# PLL.net
KiCad netlist of a schematic drawn in Altium Designer
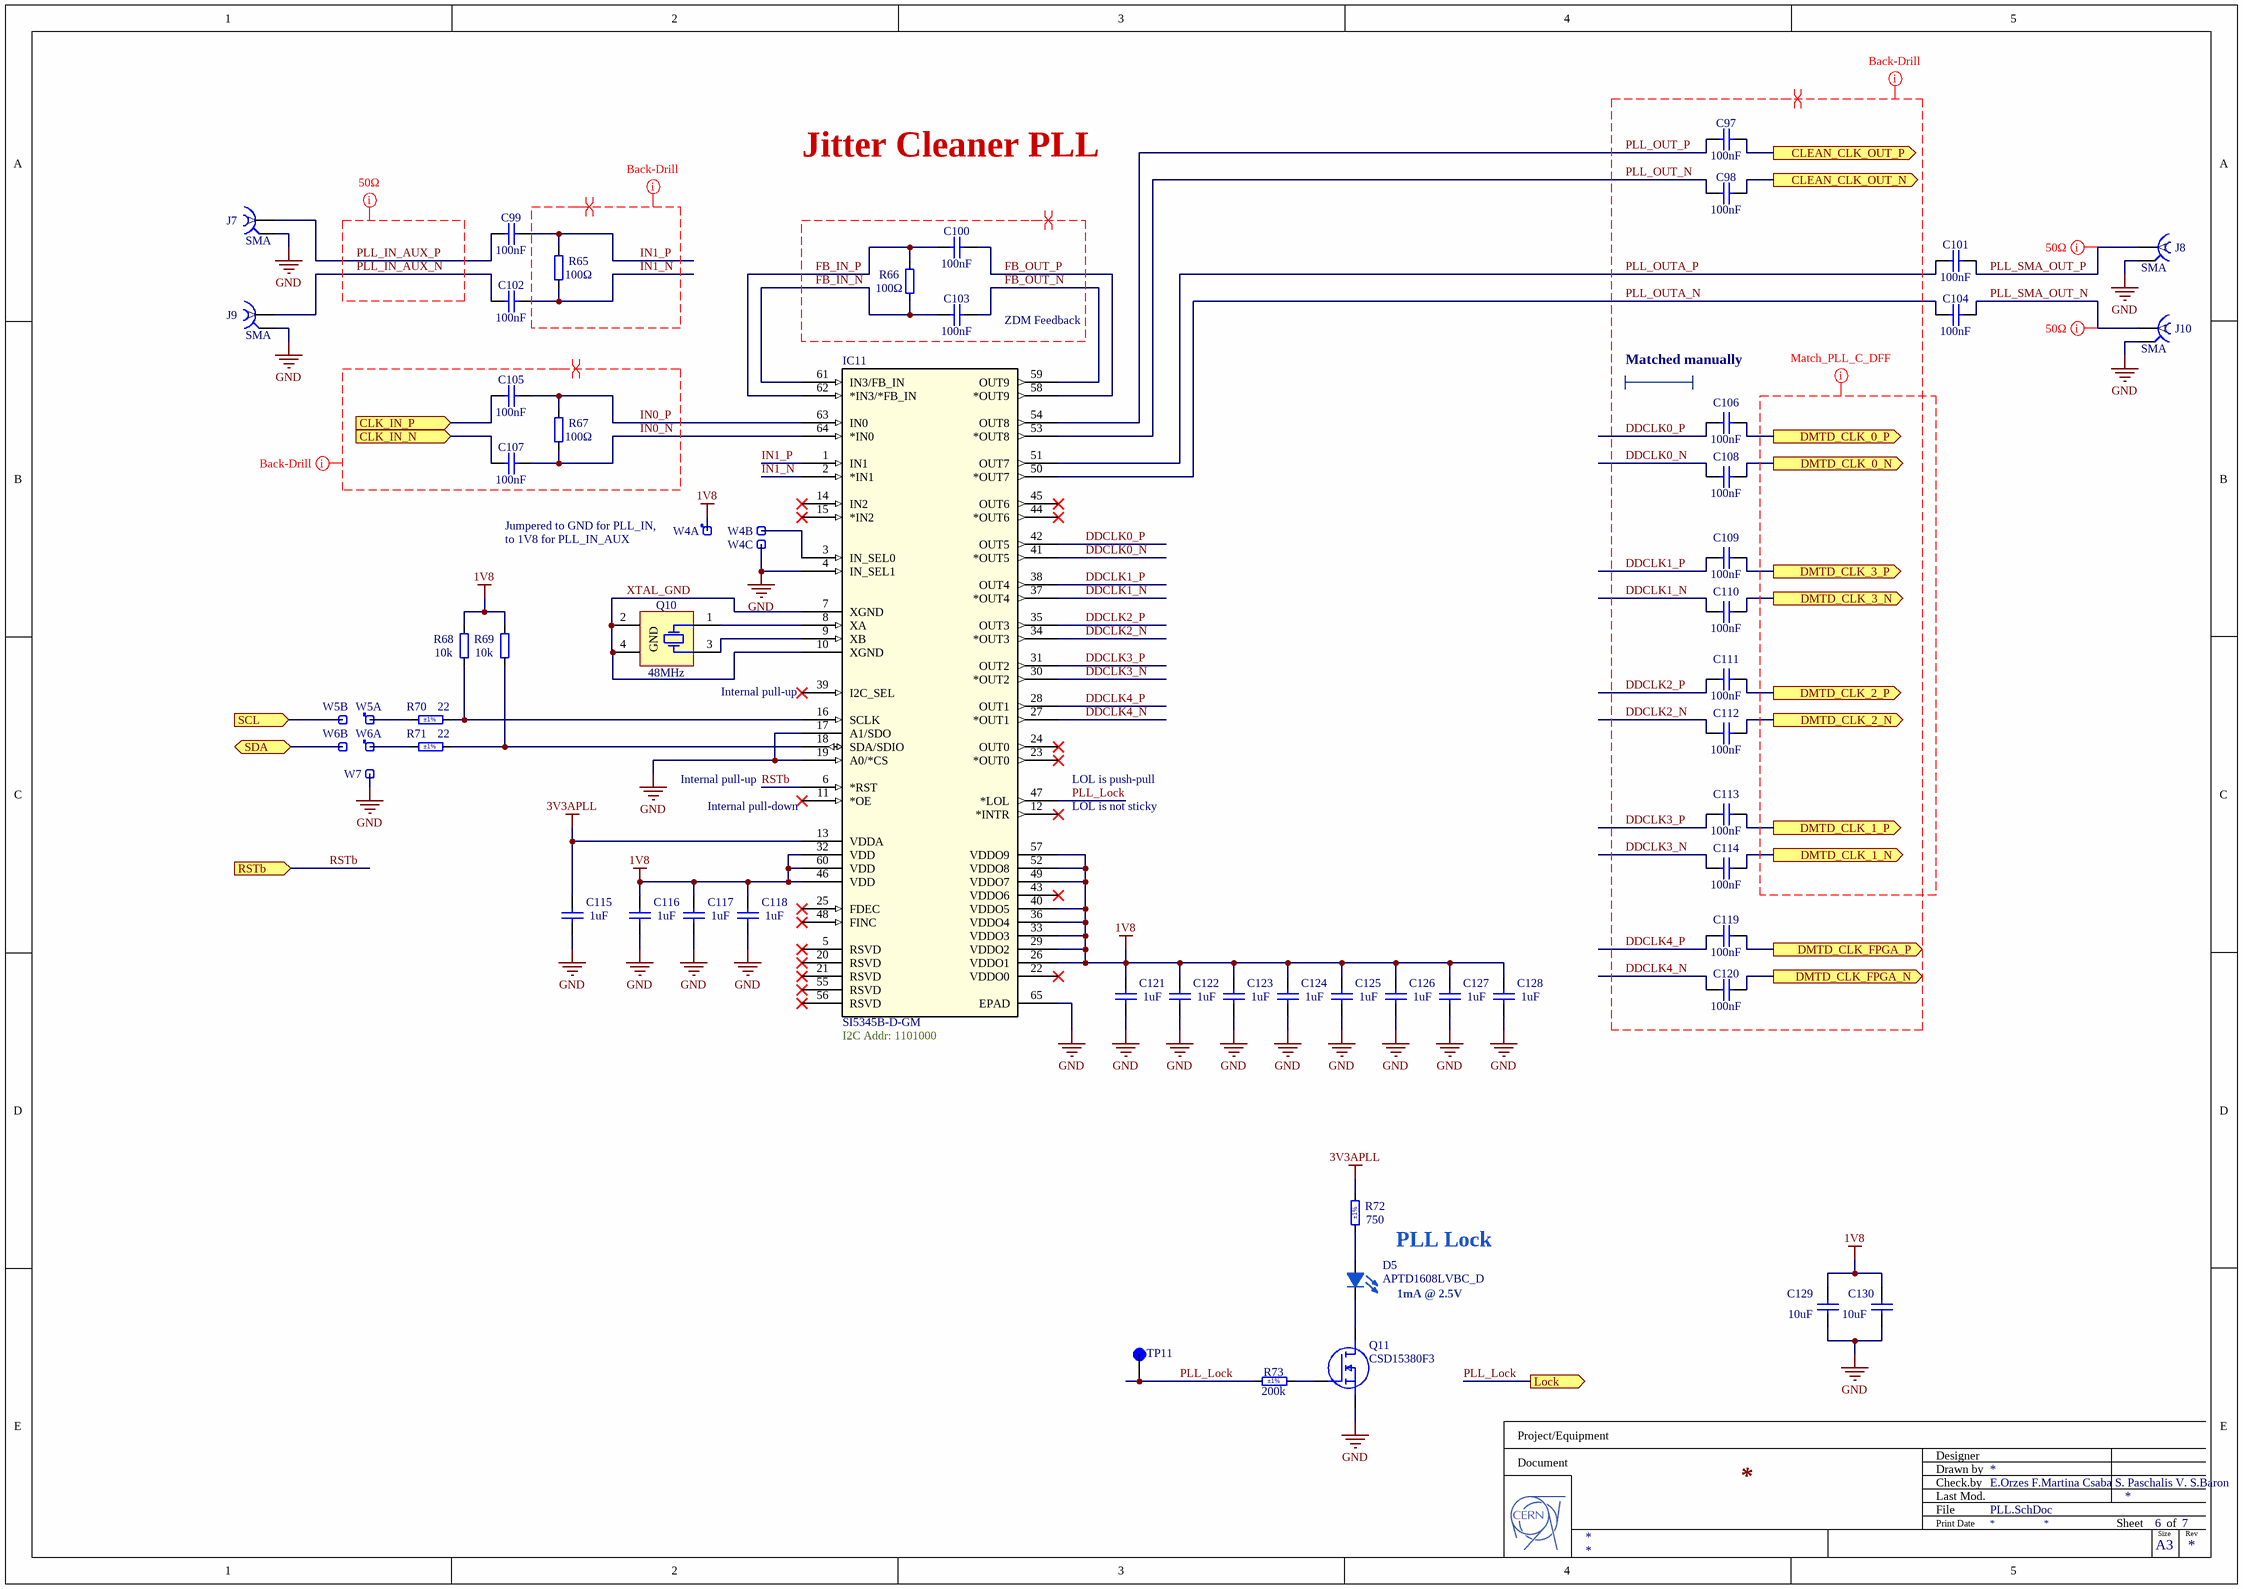
[diagram p0: PLL.SchDoc]

(export (version "E")
  (design (tool "Eeschema 10.0.6"))
  (components
    (comp (ref "C97")
      (value "100nF")
      (footprint "MURATA_HI_DENSITY_0201")
      (description "GRM033R61C104KE14")
      (libsource (lib "schLib") (part "C0201-100nF-high-density"))
    )
    (comp (ref "C98")
      (value "100nF")
      (footprint "MURATA_HI_DENSITY_0201")
      (description "GRM033R61C104KE14")
      (libsource (lib "schLib") (part "C0201-100nF-high-density"))
    )
    (comp (ref "C99")
      (value "100nF")
      (footprint "MURATA_HI_DENSITY_0201")
      (description "GRM033R61C104KE14")
      (libsource (lib "schLib") (part "C0201-100nF-high-density"))
    )
    (comp (ref "C100")
      (value "100nF")
      (footprint "MURATA_HI_DENSITY_0201")
      (description "GRM033R61C104KE14")
      (libsource (lib "schLib") (part "C0201-100nF-high-density"))
    )
    (comp (ref "C101")
      (value "100nF")
      (footprint "MURATA_HI_DENSITY_0201")
      (description "GRM033R61C104KE14")
      (libsource (lib "schLib") (part "C0201-100nF-high-density"))
    )
    (comp (ref "C102")
      (value "100nF")
      (footprint "MURATA_HI_DENSITY_0201")
      (description "GRM033R61C104KE14")
      (libsource (lib "schLib") (part "C0201-100nF-high-density"))
    )
    (comp (ref "C103")
      (value "100nF")
      (footprint "MURATA_HI_DENSITY_0201")
      (description "GRM033R61C104KE14")
      (libsource (lib "schLib") (part "C0201-100nF-high-density"))
    )
    (comp (ref "C104")
      (value "100nF")
      (footprint "MURATA_HI_DENSITY_0201")
      (description "GRM033R61C104KE14")
      (libsource (lib "schLib") (part "C0201-100nF-high-density"))
    )
    (comp (ref "C105")
      (value "100nF")
      (footprint "MURATA_HI_DENSITY_0201")
      (description "GRM033R61C104KE14")
      (libsource (lib "schLib") (part "C0201-100nF-high-density"))
    )
    (comp (ref "C106")
      (value "100nF")
      (footprint "MURATA_HI_DENSITY_0201")
      (description "GRM033R61C104KE14")
      (libsource (lib "schLib") (part "C0201-100nF-high-density"))
    )
    (comp (ref "C107")
      (value "100nF")
      (footprint "MURATA_HI_DENSITY_0201")
      (description "GRM033R61C104KE14")
      (libsource (lib "schLib") (part "C0201-100nF-high-density"))
    )
    (comp (ref "C108")
      (value "100nF")
      (footprint "MURATA_HI_DENSITY_0201")
      (description "GRM033R61C104KE14")
      (libsource (lib "schLib") (part "C0201-100nF-high-density"))
    )
    (comp (ref "C109")
      (value "100nF")
      (footprint "MURATA_HI_DENSITY_0201")
      (description "GRM033R61C104KE14")
      (libsource (lib "schLib") (part "C0201-100nF-high-density"))
    )
    (comp (ref "C110")
      (value "100nF")
      (footprint "MURATA_HI_DENSITY_0201")
      (description "GRM033R61C104KE14")
      (libsource (lib "schLib") (part "C0201-100nF-high-density"))
    )
    (comp (ref "C111")
      (value "100nF")
      (footprint "MURATA_HI_DENSITY_0201")
      (description "GRM033R61C104KE14")
      (libsource (lib "schLib") (part "C0201-100nF-high-density"))
    )
    (comp (ref "C112")
      (value "100nF")
      (footprint "MURATA_HI_DENSITY_0201")
      (description "GRM033R61C104KE14")
      (libsource (lib "schLib") (part "C0201-100nF-high-density"))
    )
    (comp (ref "C113")
      (value "100nF")
      (footprint "MURATA_HI_DENSITY_0201")
      (description "GRM033R61C104KE14")
      (libsource (lib "schLib") (part "C0201-100nF-high-density"))
    )
    (comp (ref "C114")
      (value "100nF")
      (footprint "MURATA_HI_DENSITY_0201")
      (description "GRM033R61C104KE14")
      (libsource (lib "schLib") (part "C0201-100nF-high-density"))
    )
    (comp (ref "C115")
      (value "1uF")
      (footprint "CAPC1005X55N")
      (description "GRM153B30J105ME15")
      (fields
        (field (name "PART NUMBER") "CC0402_1UF_16V_10%_X5R")
        (field (name "VOLTAGE") "16V")
        (field (name "AUTHOR") "CERN DEM JLC")
      )
      (libsource (lib "Capacitors") (part "Capacitor - non polarized"))
    )
    (comp (ref "C116")
      (value "1uF")
      (footprint "CAPC1005X55N")
      (description "GRM153B30J105ME15")
      (fields
        (field (name "PART NUMBER") "CC0402_1UF_16V_10%_X5R")
        (field (name "VOLTAGE") "16V")
        (field (name "AUTHOR") "CERN DEM JLC")
      )
      (libsource (lib "Capacitors") (part "Capacitor - non polarized"))
    )
    (comp (ref "C117")
      (value "1uF")
      (footprint "CAPC1005X55N")
      (description "GRM153B30J105ME15")
      (fields
        (field (name "PART NUMBER") "CC0402_1UF_16V_10%_X5R")
        (field (name "VOLTAGE") "16V")
        (field (name "AUTHOR") "CERN DEM JLC")
      )
      (libsource (lib "Capacitors") (part "Capacitor - non polarized"))
    )
    (comp (ref "C118")
      (value "1uF")
      (footprint "CAPC1005X55N")
      (description "GRM153B30J105ME15")
      (fields
        (field (name "PART NUMBER") "CC0402_1UF_16V_10%_X5R")
        (field (name "VOLTAGE") "16V")
        (field (name "AUTHOR") "CERN DEM JLC")
      )
      (libsource (lib "Capacitors") (part "Capacitor - non polarized"))
    )
    (comp (ref "C119")
      (value "100nF")
      (footprint "MURATA_HI_DENSITY_0201")
      (description "GRM033R61C104KE14")
      (libsource (lib "schLib") (part "C0201-100nF-high-density"))
    )
    (comp (ref "C120")
      (value "100nF")
      (footprint "MURATA_HI_DENSITY_0201")
      (description "GRM033R61C104KE14")
      (libsource (lib "schLib") (part "C0201-100nF-high-density"))
    )
    (comp (ref "C121")
      (value "1uF")
      (footprint "CAPC1005X55N")
      (description "GRM153B30J105ME15")
      (fields
        (field (name "PART NUMBER") "CC0402_1UF_16V_10%_X5R")
        (field (name "VOLTAGE") "16V")
        (field (name "AUTHOR") "CERN DEM JLC")
      )
      (libsource (lib "Capacitors") (part "Capacitor - non polarized"))
    )
    (comp (ref "C122")
      (value "1uF")
      (footprint "CAPC1005X55N")
      (description "GRM153B30J105ME15")
      (fields
        (field (name "PART NUMBER") "CC0402_1UF_16V_10%_X5R")
        (field (name "VOLTAGE") "16V")
        (field (name "AUTHOR") "CERN DEM JLC")
      )
      (libsource (lib "Capacitors") (part "Capacitor - non polarized"))
    )
    (comp (ref "C123")
      (value "1uF")
      (footprint "CAPC1005X55N")
      (description "GRM153B30J105ME15")
      (fields
        (field (name "PART NUMBER") "CC0402_1UF_16V_10%_X5R")
        (field (name "VOLTAGE") "16V")
        (field (name "AUTHOR") "CERN DEM JLC")
      )
      (libsource (lib "Capacitors") (part "Capacitor - non polarized"))
    )
    (comp (ref "C124")
      (value "1uF")
      (footprint "CAPC1005X55N")
      (description "GRM153B30J105ME15")
      (fields
        (field (name "PART NUMBER") "CC0402_1UF_16V_10%_X5R")
        (field (name "VOLTAGE") "16V")
        (field (name "AUTHOR") "CERN DEM JLC")
      )
      (libsource (lib "Capacitors") (part "Capacitor - non polarized"))
    )
    (comp (ref "C125")
      (value "1uF")
      (footprint "CAPC1005X55N")
      (description "GRM153B30J105ME15")
      (fields
        (field (name "PART NUMBER") "CC0402_1UF_16V_10%_X5R")
        (field (name "VOLTAGE") "16V")
        (field (name "AUTHOR") "CERN DEM JLC")
      )
      (libsource (lib "Capacitors") (part "Capacitor - non polarized"))
    )
    (comp (ref "C126")
      (value "1uF")
      (footprint "CAPC1005X55N")
      (description "GRM153B30J105ME15")
      (fields
        (field (name "PART NUMBER") "CC0402_1UF_16V_10%_X5R")
        (field (name "VOLTAGE") "16V")
        (field (name "AUTHOR") "CERN DEM JLC")
      )
      (libsource (lib "Capacitors") (part "Capacitor - non polarized"))
    )
    (comp (ref "C127")
      (value "1uF")
      (footprint "CAPC1005X55N")
      (description "GRM153B30J105ME15")
      (fields
        (field (name "PART NUMBER") "CC0402_1UF_16V_10%_X5R")
        (field (name "VOLTAGE") "16V")
        (field (name "AUTHOR") "CERN DEM JLC")
      )
      (libsource (lib "Capacitors") (part "Capacitor - non polarized"))
    )
    (comp (ref "C128")
      (value "1uF")
      (footprint "CAPC1005X55N")
      (description "GRM153B30J105ME15")
      (fields
        (field (name "PART NUMBER") "CC0402_1UF_16V_10%_X5R")
        (field (name "VOLTAGE") "16V")
        (field (name "AUTHOR") "CERN DEM JLC")
      )
      (libsource (lib "Capacitors") (part "Capacitor - non polarized"))
    )
    (comp (ref "C129")
      (value "10uF")
      (footprint "CAPC1608X87N")
      (description "C1608X5R1E106M080AC")
      (fields
        (field (name "PART NUMBER") "CC0603_10UF_6.3V_20%_X5R")
        (field (name "VOLTAGE") "6.3V")
        (field (name "AUTHOR") "CERN DEM JLC")
      )
      (libsource (lib "Capacitors") (part "Capacitor - non polarized"))
    )
    (comp (ref "C130")
      (value "10uF")
      (footprint "CAPC1608X87N")
      (description "C1608X5R1E106M080AC")
      (fields
        (field (name "PART NUMBER") "CC0603_10UF_6.3V_20%_X5R")
        (field (name "VOLTAGE") "6.3V")
        (field (name "AUTHOR") "CERN DEM JLC")
      )
      (libsource (lib "Capacitors") (part "Capacitor - non polarized"))
    )
    (comp (ref "D5")
      (value "APTD1608LVBC_D")
      (footprint "SamacSys:LEDC1608X110N")
      (description "LED")
      (fields
        (field (name "MANUFACTURER_PART_NUMBER") "APTD1608LVBC/D")
        (field (name "MOUSER PART NUMBER") "604-APTD1608LVBCD")
      )
      (libsource (lib "SamacSys") (part "APTD1608LVBC_D"))
    )
    (comp (ref "IC11")
      (value "SI5345B-D-GM")
      (footprint "SamacSys:QFN50P900X900X90-65N-D")
      (description "Integrated Circuit")
      (fields (field (name "MOUSER PART NUMBER") "634-SI5345B-D-GM"))
      (libsource (lib "SamacSys") (part "SI5345B-D-GM"))
    )
    (comp (ref "J7")
      (value "SMA")
      (footprint "SAMTEC_SMA-J-P-H-ST-MT1")
      (fields
        (field (name "PART NUMBER") "SAMTEC_SMA-J-P-H-ST-MT1")
        (field (name "MANUFACTURER") "SAMTEC")
        (field (name "MANUFACTURER PART NUMBER") "SMA-J-P-H-ST-MT1")
        (field (name "AUTHOR") "CERN DEM HF")
      )
      (libsource (lib "") (part "Coax_1Female_1Shield_1"))
    )
    (comp (ref "J8")
      (value "SMA")
      (footprint "SAMTEC_SMA-J-P-H-ST-MT1")
      (fields
        (field (name "PART NUMBER") "SAMTEC_SMA-J-P-H-ST-MT1")
        (field (name "MANUFACTURER") "SAMTEC")
        (field (name "MANUFACTURER PART NUMBER") "SMA-J-P-H-ST-MT1")
        (field (name "AUTHOR") "CERN DEM HF")
      )
      (libsource (lib "Connectors") (part "Coax_1Female_1Shield"))
    )
    (comp (ref "J9")
      (value "SMA")
      (footprint "SAMTEC_SMA-J-P-H-ST-MT1")
      (fields
        (field (name "PART NUMBER") "SAMTEC_SMA-J-P-H-ST-MT1")
        (field (name "MANUFACTURER") "SAMTEC")
        (field (name "MANUFACTURER PART NUMBER") "SMA-J-P-H-ST-MT1")
        (field (name "AUTHOR") "CERN DEM HF")
      )
      (libsource (lib "") (part "Coax_1Female_1Shield_1"))
    )
    (comp (ref "J10")
      (value "SMA")
      (footprint "SAMTEC_SMA-J-P-H-ST-MT1")
      (fields
        (field (name "PART NUMBER") "SAMTEC_SMA-J-P-H-ST-MT1")
        (field (name "MANUFACTURER") "SAMTEC")
        (field (name "MANUFACTURER PART NUMBER") "SMA-J-P-H-ST-MT1")
        (field (name "AUTHOR") "CERN DEM HF")
      )
      (libsource (lib "Connectors") (part "Coax_1Female_1Shield"))
    )
    (comp (ref "Q10")
      (value "48MHz")
      (footprint "XTAL_KYOCERA_CX3225SB")
      (description "Crystal 4 pins 1=XTAL Control 2=GND3=XTAL 4=GND")
      (fields
        (field (name "PART NUMBER") "XTAL_48MHZ_KYOCERA_CX3225SB48000D0FPJC1")
        (field (name "MANUFACTURER") "KYOCERA")
        (field (name "AUTHOR") "CERN DEM JLC")
      )
      (libsource (lib "ICs And Semiconductors") (part "Quartz Crystal 1X 2GND 3X 4GND"))
    )
    (comp (ref "Q11")
      (value "CSD15380F3")
      (footprint "SamacSys:CSD15380F3")
      (description "MOSFET (N-Channel)")
      (fields (field (name "MOUSER PART NUMBER") "595-CSD15380F3"))
      (libsource (lib "*") (part "CSD15380F3"))
    )
    (comp (ref "R65")
      (value "100Ω")
      (footprint "MURATA_HI_DENSITY_0201")
      (description "Resistor")
      (libsource (lib "schLib") (part "R0201-100ohm-high-density"))
    )
    (comp (ref "R66")
      (value "100Ω")
      (footprint "MURATA_HI_DENSITY_0201")
      (description "Resistor")
      (libsource (lib "schLib") (part "R0201-100ohm-high-density"))
    )
    (comp (ref "R67")
      (value "100Ω")
      (footprint "MURATA_HI_DENSITY_0201")
      (description "Resistor")
      (libsource (lib "schLib") (part "R0201-100ohm-high-density"))
    )
    (comp (ref "R68")
      (value "10k")
      (footprint "MURATA_HI_DENSITY_0201")
      (description "Resistor 10k")
      (libsource (lib "schLib") (part "R0201-100ohm-high-density"))
    )
    (comp (ref "R69")
      (value "10k")
      (footprint "MURATA_HI_DENSITY_0201")
      (description "Resistor 10k")
      (libsource (lib "schLib") (part "R0201-100ohm-high-density"))
    )
    (comp (ref "R70")
      (value "22")
      (footprint "RESC1005X40N")
      (description "Resistor - 1%")
      (fields
        (field (name "TOLERANCE") "±1%")
        (field (name "PART NUMBER") "R0402_22R_1%_0.0625W_100PPM")
        (field (name "POWER") "0.0625W")
        (field (name "AUTHOR") "CERN DEM JLC")
      )
      (libsource (lib "Resistors") (part "Resistor - 1%"))
    )
    (comp (ref "R71")
      (value "22")
      (footprint "RESC1005X40N")
      (description "Resistor - 1%")
      (fields
        (field (name "TOLERANCE") "±1%")
        (field (name "PART NUMBER") "R0402_22R_1%_0.0625W_100PPM")
        (field (name "POWER") "0.0625W")
        (field (name "AUTHOR") "CERN DEM JLC")
      )
      (libsource (lib "Resistors") (part "Resistor - 1%"))
    )
    (comp (ref "R72")
      (value "750")
      (footprint "RESC1005X40N")
      (description "Resistor - 1%")
      (fields
        (field (name "TOLERANCE") "±1%")
        (field (name "PART NUMBER") "R0402_750R_1%_0.0625W_100PPM")
        (field (name "POWER") "0.0625W")
        (field (name "AUTHOR") "CERN DEM JLC")
      )
      (libsource (lib "Resistors") (part "Resistor - 1%"))
    )
    (comp (ref "R73")
      (value "200k")
      (footprint "RESC1005X40N")
      (description "Resistor - 1%")
      (fields
        (field (name "TOLERANCE") "±1%")
        (field (name "PART NUMBER") "R0402_200K_1%_0.0625W_100PPM")
        (field (name "POWER") "0.0625W")
        (field (name "AUTHOR") "CERN DEM JLC")
      )
      (libsource (lib "Resistors") (part "Resistor - 1%"))
    )
    (comp (ref "TP11")
      (value "RCU-0C")
      (footprint "TP+195X110")
      (fields (field (name "MF") "{'manufacturer': u'TE Connectivity AMP Connectors'}"))
      (libsource (lib "RCU-0C") (part "RCU-0C"))
    )
    (comp (ref "W4")
      (value "Header 3")
      (footprint "SAMTEC_HTSW-103-23-L-S")
      (description "3 Mini Wire-Wrap Contact Strip Header")
      (fields
        (field (name "PART NUMBER") "SAMTEC_HTSW-103-23-L-S")
        (field (name "MANUFACTURER") "SAMTEC")
        (field (name "AUTHOR") "CERN DEM JLC")
      )
      (libsource (lib "Connectors") (part "Wire-Wrap Contact x3"))
    )
    (comp (ref "W5")
      (value "Header 2")
      (footprint "SAMTEC_HTSW-102-23-L-S")
      (description "2 Mini Wire-Wrap Contact Strip Header")
      (fields
        (field (name "PART NUMBER") "SAMTEC_HTSW-102-23-L-S")
        (field (name "MANUFACTURER") "SAMTEC")
        (field (name "AUTHOR") "CERN DEM JLC")
      )
      (libsource (lib "Connectors") (part "Wire-Wrap Contact x2"))
    )
    (comp (ref "W6")
      (value "Header 2")
      (footprint "SAMTEC_HTSW-102-23-L-S")
      (description "2 Mini Wire-Wrap Contact Strip Header")
      (fields
        (field (name "PART NUMBER") "SAMTEC_HTSW-102-23-L-S")
        (field (name "MANUFACTURER") "SAMTEC")
        (field (name "AUTHOR") "CERN DEM JLC")
      )
      (libsource (lib "Connectors") (part "Wire-Wrap Contact x2"))
    )
    (comp (ref "W7")
      (value "Header 1")
      (footprint "SAMTEC_HTSW-101-23-L-S")
      (description "Single Mini Wire-Wrap Contact")
      (fields
        (field (name "PART NUMBER") "SAMTEC_HTSW-101-23-L-S")
        (field (name "MANUFACTURER") "SAMTEC")
        (field (name "AUTHOR") "CERN DEM JLC")
      )
      (libsource (lib "Connectors") (part "Wire-Wrap Contact"))
    )
  )
  (nets
    (net (code "1") (name "/CLEAN_CLK_OUT_N") (class "Default")
      (node (ref "C98") (pin "2") (pinfunction "2_2") (pintype "passive"))
    )
    (net (code "2") (name "/CLEAN_CLK_OUT_P") (class "Default")
      (node (ref "C97") (pin "2") (pinfunction "2_2") (pintype "passive"))
    )
    (net (code "3") (name "/CLK_IN_N") (class "Default")
      (node (ref "C107") (pin "2") (pinfunction "2_2") (pintype "passive"))
    )
    (net (code "4") (name "/CLK_IN_P") (class "Default")
      (node (ref "C105") (pin "2") (pinfunction "2_2") (pintype "passive"))
    )
    (net (code "5") (name "/DDCLK0_N") (class "Default")
      (node (ref "C108") (pin "1") (pinfunction "1_1") (pintype "passive"))
      (node (ref "IC11") (pin "41") (pinfunction "*OUT5_41") (pintype "output"))
    )
    (net (code "6") (name "/DDCLK0_P") (class "Default")
      (node (ref "C106") (pin "1") (pinfunction "1_1") (pintype "passive"))
      (node (ref "IC11") (pin "42") (pinfunction "OUT5_42") (pintype "output"))
    )
    (net (code "7") (name "/DDCLK1_N") (class "Default")
      (node (ref "C110") (pin "1") (pinfunction "1_1") (pintype "passive"))
      (node (ref "IC11") (pin "37") (pinfunction "*OUT4_37") (pintype "output"))
    )
    (net (code "8") (name "/DDCLK1_P") (class "Default")
      (node (ref "C109") (pin "1") (pinfunction "1_1") (pintype "passive"))
      (node (ref "IC11") (pin "38") (pinfunction "OUT4_38") (pintype "output"))
    )
    (net (code "9") (name "/DDCLK2_N") (class "Default")
      (node (ref "C112") (pin "1") (pinfunction "1_1") (pintype "passive"))
      (node (ref "IC11") (pin "34") (pinfunction "*OUT3_34") (pintype "output"))
    )
    (net (code "10") (name "/DDCLK2_P") (class "Default")
      (node (ref "C111") (pin "1") (pinfunction "1_1") (pintype "passive"))
      (node (ref "IC11") (pin "35") (pinfunction "OUT3_35") (pintype "output"))
    )
    (net (code "11") (name "/DDCLK3_N") (class "Default")
      (node (ref "C114") (pin "1") (pinfunction "1_1") (pintype "passive"))
      (node (ref "IC11") (pin "30") (pinfunction "*OUT2_30") (pintype "output"))
    )
    (net (code "12") (name "/DDCLK3_P") (class "Default")
      (node (ref "C113") (pin "1") (pinfunction "1_1") (pintype "passive"))
      (node (ref "IC11") (pin "31") (pinfunction "OUT2_31") (pintype "output"))
    )
    (net (code "13") (name "/DDCLK4_N") (class "Default")
      (node (ref "C120") (pin "1") (pinfunction "1_1") (pintype "passive"))
      (node (ref "IC11") (pin "27") (pinfunction "*OUT1_27") (pintype "output"))
    )
    (net (code "14") (name "/DDCLK4_P") (class "Default")
      (node (ref "C119") (pin "1") (pinfunction "1_1") (pintype "passive"))
      (node (ref "IC11") (pin "28") (pinfunction "OUT1_28") (pintype "output"))
    )
    (net (code "15") (name "/DMTD_CLK_0_N") (class "Default")
      (node (ref "C108") (pin "2") (pinfunction "2_2") (pintype "passive"))
    )
    (net (code "16") (name "/DMTD_CLK_0_P") (class "Default")
      (node (ref "C106") (pin "2") (pinfunction "2_2") (pintype "passive"))
    )
    (net (code "17") (name "/DMTD_CLK_1_N") (class "Default")
      (node (ref "C114") (pin "2") (pinfunction "2_2") (pintype "passive"))
    )
    (net (code "18") (name "/DMTD_CLK_1_P") (class "Default")
      (node (ref "C113") (pin "2") (pinfunction "2_2") (pintype "passive"))
    )
    (net (code "19") (name "/DMTD_CLK_2_N") (class "Default")
      (node (ref "C112") (pin "2") (pinfunction "2_2") (pintype "passive"))
    )
    (net (code "20") (name "/DMTD_CLK_2_P") (class "Default")
      (node (ref "C111") (pin "2") (pinfunction "2_2") (pintype "passive"))
    )
    (net (code "21") (name "/DMTD_CLK_3_N") (class "Default")
      (node (ref "C110") (pin "2") (pinfunction "2_2") (pintype "passive"))
    )
    (net (code "22") (name "/DMTD_CLK_3_P") (class "Default")
      (node (ref "C109") (pin "2") (pinfunction "2_2") (pintype "passive"))
    )
    (net (code "23") (name "/DMTD_CLK_FPGA_N") (class "Default")
      (node (ref "C120") (pin "2") (pinfunction "2_2") (pintype "passive"))
    )
    (net (code "24") (name "/DMTD_CLK_FPGA_P") (class "Default")
      (node (ref "C119") (pin "2") (pinfunction "2_2") (pintype "passive"))
    )
    (net (code "25") (name "/FB_IN_N") (class "Default")
      (node (ref "C103") (pin "1") (pinfunction "1_1") (pintype "passive"))
      (node (ref "IC11") (pin "61") (pinfunction "IN3/FB_IN_61") (pintype "input"))
      (node (ref "R66") (pin "1") (pinfunction "1_1") (pintype "passive"))
    )
    (net (code "26") (name "/FB_IN_P") (class "Default")
      (node (ref "C100") (pin "1") (pinfunction "1_1") (pintype "passive"))
      (node (ref "IC11") (pin "62") (pinfunction "*IN3/*FB_IN_62") (pintype "input"))
      (node (ref "R66") (pin "2") (pinfunction "2_2") (pintype "passive"))
    )
    (net (code "27") (name "/FB_OUT_N") (class "Default")
      (node (ref "C103") (pin "2") (pinfunction "2_2") (pintype "passive"))
      (node (ref "IC11") (pin "59") (pinfunction "OUT9_59") (pintype "output"))
    )
    (net (code "28") (name "/FB_OUT_P") (class "Default")
      (node (ref "C100") (pin "2") (pinfunction "2_2") (pintype "passive"))
      (node (ref "IC11") (pin "58") (pinfunction "*OUT9_58") (pintype "output"))
    )
    (net (code "29") (name "/IN0_N") (class "Default")
      (node (ref "C107") (pin "1") (pinfunction "1_1") (pintype "passive"))
      (node (ref "IC11") (pin "64") (pinfunction "*IN0_64") (pintype "input"))
      (node (ref "R67") (pin "1") (pinfunction "1_1") (pintype "passive"))
    )
    (net (code "30") (name "/IN0_P") (class "Default")
      (node (ref "C105") (pin "1") (pinfunction "1_1") (pintype "passive"))
      (node (ref "IC11") (pin "63") (pinfunction "IN0_63") (pintype "input"))
      (node (ref "R67") (pin "2") (pinfunction "2_2") (pintype "passive"))
    )
    (net (code "31") (name "/IN1_N") (class "Default")
      (node (ref "C102") (pin "1") (pinfunction "1_1") (pintype "passive"))
      (node (ref "IC11") (pin "2") (pinfunction "*IN1_2") (pintype "input"))
      (node (ref "R65") (pin "1") (pinfunction "1_1") (pintype "passive"))
    )
    (net (code "32") (name "/IN1_P") (class "Default")
      (node (ref "C99") (pin "1") (pinfunction "1_1") (pintype "passive"))
      (node (ref "IC11") (pin "1") (pinfunction "IN1_1") (pintype "input"))
      (node (ref "R65") (pin "2") (pinfunction "2_2") (pintype "passive"))
    )
    (net (code "33") (name "/PLL_IN_AUX_N") (class "Default")
      (node (ref "C102") (pin "2") (pinfunction "2_2") (pintype "passive"))
      (node (ref "J9") (pin "1") (pinfunction "1_1") (pintype "output"))
    )
    (net (code "34") (name "/PLL_IN_AUX_P") (class "Default")
      (node (ref "C99") (pin "2") (pinfunction "2_2") (pintype "passive"))
      (node (ref "J7") (pin "1") (pinfunction "1_1") (pintype "output"))
    )
    (net (code "35") (name "/PLL_Lock") (class "Default")
      (node (ref "IC11") (pin "47") (pinfunction "*LOL_47") (pintype "output"))
      (node (ref "R73") (pin "1") (pinfunction "1_1") (pintype "passive"))
      (node (ref "TP11") (pin "1") (pinfunction "TP_1") (pintype "passive"))
    )
    (net (code "36") (name "/PLL_OUTA_N") (class "Default")
      (node (ref "C104") (pin "1") (pinfunction "1_1") (pintype "passive"))
      (node (ref "IC11") (pin "50") (pinfunction "*OUT7_50") (pintype "output"))
    )
    (net (code "37") (name "/PLL_OUTA_P") (class "Default")
      (node (ref "C101") (pin "1") (pinfunction "1_1") (pintype "passive"))
      (node (ref "IC11") (pin "51") (pinfunction "OUT7_51") (pintype "output"))
    )
    (net (code "38") (name "/PLL_OUT_N") (class "Default")
      (node (ref "C98") (pin "1") (pinfunction "1_1") (pintype "passive"))
      (node (ref "IC11") (pin "53") (pinfunction "*OUT8_53") (pintype "output"))
    )
    (net (code "39") (name "/PLL_OUT_P") (class "Default")
      (node (ref "C97") (pin "1") (pinfunction "1_1") (pintype "passive"))
      (node (ref "IC11") (pin "54") (pinfunction "OUT8_54") (pintype "output"))
    )
    (net (code "40") (name "/PLL_SMA_OUT_N") (class "Default")
      (node (ref "C104") (pin "2") (pinfunction "2_2") (pintype "passive"))
      (node (ref "J10") (pin "1") (pinfunction "1_1") (pintype "output"))
    )
    (net (code "41") (name "/PLL_SMA_OUT_P") (class "Default")
      (node (ref "C101") (pin "2") (pinfunction "2_2") (pintype "passive"))
      (node (ref "J8") (pin "1") (pinfunction "1_1") (pintype "output"))
    )
    (net (code "42") (name "/RSTb") (class "Default")
      (node (ref "IC11") (pin "6") (pinfunction "*RST_6") (pintype "input"))
    )
    (net (code "43") (name "/SCL") (class "Default")
      (node (ref "W5") (pin "2") (pinfunction "2_2") (pintype "passive"))
    )
    (net (code "44") (name "/SDA") (class "Default")
      (node (ref "W6") (pin "2") (pinfunction "2_2") (pintype "passive"))
    )
    (net (code "45") (name "/XTAL_GND") (class "Default")
      (node (ref "IC11") (pin "10") (pinfunction "XGND_10") (pintype "power_in"))
      (node (ref "IC11") (pin "7") (pinfunction "XGND_7") (pintype "power_in"))
      (node (ref "Q10") (pin "2") (pinfunction "GND_2") (pintype "power_in"))
      (node (ref "Q10") (pin "4") (pinfunction "GND_4") (pintype "power_in"))
    )
    (net (code "46") (name "1V8") (class "Default")
      (node (ref "C116") (pin "2") (pinfunction "2_2") (pintype "passive"))
      (node (ref "C117") (pin "2") (pinfunction "2_2") (pintype "passive"))
      (node (ref "C118") (pin "2") (pinfunction "2_2") (pintype "passive"))
      (node (ref "C121") (pin "2") (pinfunction "2_2") (pintype "passive"))
      (node (ref "C122") (pin "2") (pinfunction "2_2") (pintype "passive"))
      (node (ref "C123") (pin "2") (pinfunction "2_2") (pintype "passive"))
      (node (ref "C124") (pin "2") (pinfunction "2_2") (pintype "passive"))
      (node (ref "C125") (pin "2") (pinfunction "2_2") (pintype "passive"))
      (node (ref "C126") (pin "2") (pinfunction "2_2") (pintype "passive"))
      (node (ref "C127") (pin "2") (pinfunction "2_2") (pintype "passive"))
      (node (ref "C128") (pin "2") (pinfunction "2_2") (pintype "passive"))
      (node (ref "C129") (pin "2") (pinfunction "2_2") (pintype "passive"))
      (node (ref "C130") (pin "2") (pinfunction "2_2") (pintype "passive"))
      (node (ref "IC11") (pin "26") (pinfunction "VDDO1_26") (pintype "power_in"))
      (node (ref "IC11") (pin "29") (pinfunction "VDDO2_29") (pintype "power_in"))
      (node (ref "IC11") (pin "32") (pinfunction "VDD_32") (pintype "power_in"))
      (node (ref "IC11") (pin "33") (pinfunction "VDDO3_33") (pintype "power_in"))
      (node (ref "IC11") (pin "36") (pinfunction "VDDO4_36") (pintype "power_in"))
      (node (ref "IC11") (pin "40") (pinfunction "VDDO5_40") (pintype "power_in"))
      (node (ref "IC11") (pin "46") (pinfunction "VDD_46") (pintype "power_in"))
      (node (ref "IC11") (pin "49") (pinfunction "VDDO7_49") (pintype "power_in"))
      (node (ref "IC11") (pin "52") (pinfunction "VDDO8_52") (pintype "power_in"))
      (node (ref "IC11") (pin "57") (pinfunction "VDDO9_57") (pintype "power_in"))
      (node (ref "IC11") (pin "60") (pinfunction "VDD_60") (pintype "power_in"))
      (node (ref "R68") (pin "2") (pinfunction "2_2") (pintype "passive"))
      (node (ref "R69") (pin "2") (pinfunction "2_2") (pintype "passive"))
      (node (ref "W4") (pin "1") (pinfunction "1_1") (pintype "passive"))
    )
    (net (code "47") (name "3V3APLL") (class "Default")
      (node (ref "C115") (pin "2") (pinfunction "2_2") (pintype "passive"))
      (node (ref "IC11") (pin "13") (pinfunction "VDDA_13") (pintype "power_in"))
      (node (ref "R72") (pin "2") (pinfunction "2_2") (pintype "passive"))
    )
    (net (code "48") (name "GND") (class "Default")
      (node (ref "C115") (pin "1") (pinfunction "1_1") (pintype "passive"))
      (node (ref "C116") (pin "1") (pinfunction "1_1") (pintype "passive"))
      (node (ref "C117") (pin "1") (pinfunction "1_1") (pintype "passive"))
      (node (ref "C118") (pin "1") (pinfunction "1_1") (pintype "passive"))
      (node (ref "C121") (pin "1") (pinfunction "1_1") (pintype "passive"))
      (node (ref "C122") (pin "1") (pinfunction "1_1") (pintype "passive"))
      (node (ref "C123") (pin "1") (pinfunction "1_1") (pintype "passive"))
      (node (ref "C124") (pin "1") (pinfunction "1_1") (pintype "passive"))
      (node (ref "C125") (pin "1") (pinfunction "1_1") (pintype "passive"))
      (node (ref "C126") (pin "1") (pinfunction "1_1") (pintype "passive"))
      (node (ref "C127") (pin "1") (pinfunction "1_1") (pintype "passive"))
      (node (ref "C128") (pin "1") (pinfunction "1_1") (pintype "passive"))
      (node (ref "C129") (pin "1") (pinfunction "1_1") (pintype "passive"))
      (node (ref "C130") (pin "1") (pinfunction "1_1") (pintype "passive"))
      (node (ref "IC11") (pin "17") (pinfunction "A1/SDO_17") (pintype "passive"))
      (node (ref "IC11") (pin "19") (pinfunction "A0/*CS_19") (pintype "input"))
      (node (ref "IC11") (pin "4") (pinfunction "IN_SEL1_4") (pintype "input"))
      (node (ref "IC11") (pin "65") (pinfunction "EPAD_65") (pintype "passive"))
      (node (ref "J10") (pin "2") (pinfunction "2_2") (pintype "power_in"))
      (node (ref "J7") (pin "2") (pinfunction "2_2") (pintype "power_in"))
      (node (ref "J8") (pin "2") (pinfunction "2_2") (pintype "power_in"))
      (node (ref "J9") (pin "2") (pinfunction "2_2") (pintype "power_in"))
      (node (ref "Q11") (pin "2") (pinfunction "S_2") (pintype "passive"))
      (node (ref "W4") (pin "3") (pinfunction "3_3") (pintype "bidirectional"))
      (node (ref "W7") (pin "1") (pinfunction "1_1") (pintype "passive"))
    )
    (net (code "49") (name "Net-(D5-A)") (class "Default")
      (node (ref "D5") (pin "2") (pinfunction "A_2") (pintype "passive"))
      (node (ref "R72") (pin "1") (pinfunction "1_1") (pintype "passive"))
    )
    (net (code "50") (name "Net-(D5-K)") (class "Default")
      (node (ref "D5") (pin "1") (pinfunction "K_1") (pintype "passive"))
      (node (ref "Q11") (pin "3") (pinfunction "D_3") (pintype "passive"))
    )
    (net (code "51") (name "Net-(IC11-IN_SEL0)") (class "Default")
      (node (ref "IC11") (pin "3") (pinfunction "IN_SEL0_3") (pintype "input"))
      (node (ref "W4") (pin "2") (pinfunction "2_2") (pintype "bidirectional"))
    )
    (net (code "52") (name "Net-(IC11-SCLK)") (class "Default")
      (node (ref "IC11") (pin "16") (pinfunction "SCLK_16") (pintype "input"))
      (node (ref "R68") (pin "1") (pinfunction "1_1") (pintype "passive"))
      (node (ref "R70") (pin "2") (pinfunction "2_2") (pintype "passive"))
    )
    (net (code "53") (name "Net-(IC11-SDA{slash}SDIO)") (class "Default")
      (node (ref "IC11") (pin "18") (pinfunction "SDA/SDIO_18") (pintype "bidirectional"))
      (node (ref "R69") (pin "1") (pinfunction "1_1") (pintype "passive"))
      (node (ref "R71") (pin "2") (pinfunction "2_2") (pintype "passive"))
    )
    (net (code "54") (name "Net-(IC11-XA)") (class "Default")
      (node (ref "IC11") (pin "8") (pinfunction "XA_8") (pintype "input"))
      (node (ref "Q10") (pin "1") (pinfunction "X_1") (pintype "passive"))
    )
    (net (code "55") (name "Net-(IC11-XB)") (class "Default")
      (node (ref "IC11") (pin "9") (pinfunction "XB_9") (pintype "input"))
      (node (ref "Q10") (pin "3") (pinfunction "X_3") (pintype "passive"))
    )
    (net (code "56") (name "Net-(Q11-G)") (class "Default")
      (node (ref "Q11") (pin "1") (pinfunction "G_1") (pintype "passive"))
      (node (ref "R73") (pin "2") (pinfunction "2_2") (pintype "passive"))
    )
    (net (code "57") (name "Net-(R70-Pad1)") (class "Default")
      (node (ref "R70") (pin "1") (pinfunction "1_1") (pintype "passive"))
      (node (ref "W5") (pin "1") (pinfunction "1_1") (pintype "bidirectional"))
    )
    (net (code "58") (name "Net-(R71-Pad1)") (class "Default")
      (node (ref "R71") (pin "1") (pinfunction "1_1") (pintype "passive"))
      (node (ref "W6") (pin "1") (pinfunction "1_1") (pintype "bidirectional"))
    )
    (net (code "59") (name "unconnected-(IC11-*IN2-Pad15)") (class "Default")
      (node (ref "IC11") (pin "15") (pinfunction "*IN2_15") (pintype "input+no_connect"))
    )
    (net (code "60") (name "unconnected-(IC11-*INTR-Pad12)") (class "Default")
      (node (ref "IC11") (pin "12") (pinfunction "*INTR_12") (pintype "output+no_connect"))
    )
    (net (code "61") (name "unconnected-(IC11-*OE-Pad11)") (class "Default")
      (node (ref "IC11") (pin "11") (pinfunction "*OE_11") (pintype "input+no_connect"))
    )
    (net (code "62") (name "unconnected-(IC11-*OUT0-Pad23)") (class "Default")
      (node (ref "IC11") (pin "23") (pinfunction "*OUT0_23") (pintype "output+no_connect"))
    )
    (net (code "63") (name "unconnected-(IC11-*OUT6-Pad44)") (class "Default")
      (node (ref "IC11") (pin "44") (pinfunction "*OUT6_44") (pintype "output+no_connect"))
    )
    (net (code "64") (name "unconnected-(IC11-FDEC-Pad25)") (class "Default")
      (node (ref "IC11") (pin "25") (pinfunction "FDEC_25") (pintype "input+no_connect"))
    )
    (net (code "65") (name "unconnected-(IC11-FINC-Pad48)") (class "Default")
      (node (ref "IC11") (pin "48") (pinfunction "FINC_48") (pintype "input+no_connect"))
    )
    (net (code "66") (name "unconnected-(IC11-I2C_SEL-Pad39)") (class "Default")
      (node (ref "IC11") (pin "39") (pinfunction "I2C_SEL_39") (pintype "input+no_connect"))
    )
    (net (code "67") (name "unconnected-(IC11-IN2-Pad14)") (class "Default")
      (node (ref "IC11") (pin "14") (pinfunction "IN2_14") (pintype "input+no_connect"))
    )
    (net (code "68") (name "unconnected-(IC11-OUT0-Pad24)") (class "Default")
      (node (ref "IC11") (pin "24") (pinfunction "OUT0_24") (pintype "output+no_connect"))
    )
    (net (code "69") (name "unconnected-(IC11-OUT6-Pad45)") (class "Default")
      (node (ref "IC11") (pin "45") (pinfunction "OUT6_45") (pintype "output+no_connect"))
    )
    (net (code "70") (name "unconnected-(IC11-RSVD-Pad5)") (class "Default")
      (node (ref "IC11") (pin "5") (pinfunction "RSVD_5") (pintype "passive+no_connect"))
    )
    (net (code "71") (name "unconnected-(IC11-RSVD-Pad20)") (class "Default")
      (node (ref "IC11") (pin "20") (pinfunction "RSVD_20") (pintype "passive+no_connect"))
    )
    (net (code "72") (name "unconnected-(IC11-RSVD-Pad21)") (class "Default")
      (node (ref "IC11") (pin "21") (pinfunction "RSVD_21") (pintype "passive+no_connect"))
    )
    (net (code "73") (name "unconnected-(IC11-RSVD-Pad55)") (class "Default")
      (node (ref "IC11") (pin "55") (pinfunction "RSVD_55") (pintype "passive+no_connect"))
    )
    (net (code "74") (name "unconnected-(IC11-RSVD-Pad56)") (class "Default")
      (node (ref "IC11") (pin "56") (pinfunction "RSVD_56") (pintype "passive+no_connect"))
    )
    (net (code "75") (name "unconnected-(IC11-VDDO0-Pad22)") (class "Default")
      (node (ref "IC11") (pin "22") (pinfunction "VDDO0_22") (pintype "power_in+no_connect"))
    )
    (net (code "76") (name "unconnected-(IC11-VDDO6-Pad43)") (class "Default")
      (node (ref "IC11") (pin "43") (pinfunction "VDDO6_43") (pintype "power_in+no_connect"))
    )
  )
)
